# STHV800_breakout_board.net
KiCad netlist of a schematic drawn in EAGLE
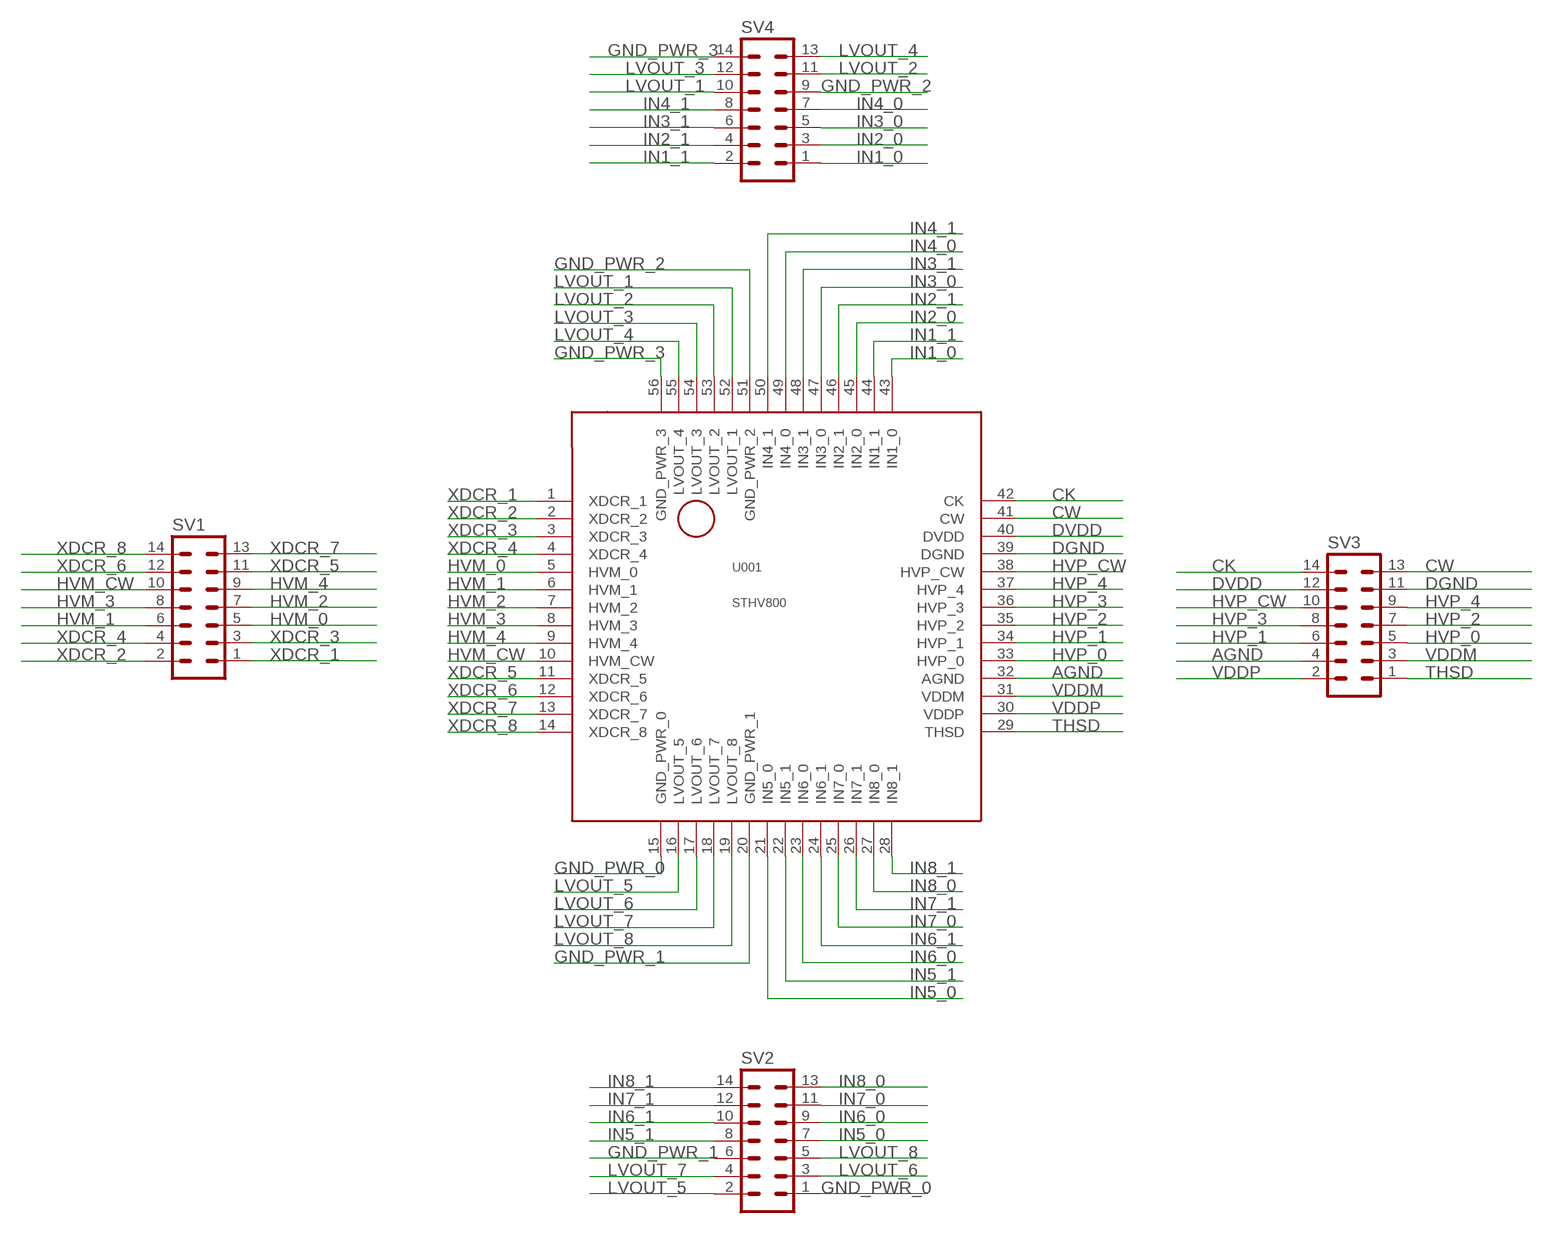
[diagram p0: schematic, sheet 1]

(export (version "E")
  (design (tool "Eeschema 10.0.6"))
  (components
    (comp (ref "SV1")
      (value "MA07-2")
      (footprint "eagle-import:MA07-2")
      (libsource (lib "eagle-import") (part "MA07-2"))
    )
    (comp (ref "SV2")
      (value "MA07-2")
      (footprint "eagle-import:MA07-2")
      (libsource (lib "eagle-import") (part "MA07-2"))
    )
    (comp (ref "SV3")
      (value "MA07-2")
      (footprint "eagle-import:MA07-2")
      (libsource (lib "eagle-import") (part "MA07-2"))
    )
    (comp (ref "SV4")
      (value "MA07-2")
      (footprint "eagle-import:MA07-2")
      (libsource (lib "eagle-import") (part "MA07-2"))
    )
    (comp (ref "U001")
      (value "STHV800")
      (footprint "eagle-import:STHV800")
      (libsource (lib "eagle-import") (part "STHV800"))
    )
  )
  (nets
    (net (code "1") (name "/AGND") (class "Default")
      (node (ref "SV3") (pin "4") (pinfunction "4_4") (pintype "passive"))
      (node (ref "U001") (pin "32") (pinfunction "AGND_32") (pintype "bidirectional"))
    )
    (net (code "2") (name "/CK") (class "Default")
      (node (ref "SV3") (pin "14") (pinfunction "14_14") (pintype "passive"))
      (node (ref "U001") (pin "42") (pinfunction "CK_42") (pintype "bidirectional"))
    )
    (net (code "3") (name "/CW") (class "Default")
      (node (ref "SV3") (pin "13") (pinfunction "13_13") (pintype "passive"))
      (node (ref "U001") (pin "41") (pinfunction "CW_41") (pintype "bidirectional"))
    )
    (net (code "4") (name "/DGND") (class "Default")
      (node (ref "SV3") (pin "11") (pinfunction "11_11") (pintype "passive"))
      (node (ref "U001") (pin "39") (pinfunction "DGND_39") (pintype "bidirectional"))
    )
    (net (code "5") (name "/DVDD") (class "Default")
      (node (ref "SV3") (pin "12") (pinfunction "12_12") (pintype "passive"))
      (node (ref "U001") (pin "40") (pinfunction "DVDD_40") (pintype "bidirectional"))
    )
    (net (code "6") (name "/GND_PWR_0") (class "Default")
      (node (ref "SV2") (pin "1") (pinfunction "1_1") (pintype "passive"))
      (node (ref "U001") (pin "15") (pinfunction "GND_PWR_0_15") (pintype "bidirectional"))
    )
    (net (code "7") (name "/GND_PWR_1") (class "Default")
      (node (ref "SV2") (pin "6") (pinfunction "6_6") (pintype "passive"))
      (node (ref "U001") (pin "20") (pinfunction "GND_PWR_1_20") (pintype "bidirectional"))
    )
    (net (code "8") (name "/GND_PWR_2") (class "Default")
      (node (ref "SV4") (pin "9") (pinfunction "9_9") (pintype "passive"))
      (node (ref "U001") (pin "51") (pinfunction "GND_PWR_2_51") (pintype "bidirectional"))
    )
    (net (code "9") (name "/GND_PWR_3") (class "Default")
      (node (ref "SV4") (pin "14") (pinfunction "14_14") (pintype "passive"))
      (node (ref "U001") (pin "56") (pinfunction "GND_PWR_3_56") (pintype "bidirectional"))
    )
    (net (code "10") (name "/HVM_0") (class "Default")
      (node (ref "SV1") (pin "5") (pinfunction "5_5") (pintype "passive"))
      (node (ref "U001") (pin "5") (pinfunction "HVM_0_5") (pintype "bidirectional"))
    )
    (net (code "11") (name "/HVM_1") (class "Default")
      (node (ref "SV1") (pin "6") (pinfunction "6_6") (pintype "passive"))
      (node (ref "U001") (pin "6") (pinfunction "HVM_1_6") (pintype "bidirectional"))
    )
    (net (code "12") (name "/HVM_2") (class "Default")
      (node (ref "SV1") (pin "7") (pinfunction "7_7") (pintype "passive"))
      (node (ref "U001") (pin "7") (pinfunction "HVM_2_7") (pintype "bidirectional"))
    )
    (net (code "13") (name "/HVM_3") (class "Default")
      (node (ref "SV1") (pin "8") (pinfunction "8_8") (pintype "passive"))
      (node (ref "U001") (pin "8") (pinfunction "HVM_3_8") (pintype "bidirectional"))
    )
    (net (code "14") (name "/HVM_4") (class "Default")
      (node (ref "SV1") (pin "9") (pinfunction "9_9") (pintype "passive"))
      (node (ref "U001") (pin "9") (pinfunction "HVM_4_9") (pintype "bidirectional"))
    )
    (net (code "15") (name "/HVM_CW") (class "Default")
      (node (ref "SV1") (pin "10") (pinfunction "10_10") (pintype "passive"))
      (node (ref "U001") (pin "10") (pinfunction "HVM_CW_10") (pintype "bidirectional"))
    )
    (net (code "16") (name "/HVP_0") (class "Default")
      (node (ref "SV3") (pin "5") (pinfunction "5_5") (pintype "passive"))
      (node (ref "U001") (pin "33") (pinfunction "HVP_0_33") (pintype "bidirectional"))
    )
    (net (code "17") (name "/HVP_1") (class "Default")
      (node (ref "SV3") (pin "6") (pinfunction "6_6") (pintype "passive"))
      (node (ref "U001") (pin "34") (pinfunction "HVP_1_34") (pintype "bidirectional"))
    )
    (net (code "18") (name "/HVP_2") (class "Default")
      (node (ref "SV3") (pin "7") (pinfunction "7_7") (pintype "passive"))
      (node (ref "U001") (pin "35") (pinfunction "HVP_2_35") (pintype "bidirectional"))
    )
    (net (code "19") (name "/HVP_3") (class "Default")
      (node (ref "SV3") (pin "8") (pinfunction "8_8") (pintype "passive"))
      (node (ref "U001") (pin "36") (pinfunction "HVP_3_36") (pintype "bidirectional"))
    )
    (net (code "20") (name "/HVP_4") (class "Default")
      (node (ref "SV3") (pin "9") (pinfunction "9_9") (pintype "passive"))
      (node (ref "U001") (pin "37") (pinfunction "HVP_4_37") (pintype "bidirectional"))
    )
    (net (code "21") (name "/HVP_CW") (class "Default")
      (node (ref "SV3") (pin "10") (pinfunction "10_10") (pintype "passive"))
      (node (ref "U001") (pin "38") (pinfunction "HVP_CW_38") (pintype "bidirectional"))
    )
    (net (code "22") (name "/IN1_0") (class "Default")
      (node (ref "SV4") (pin "1") (pinfunction "1_1") (pintype "passive"))
      (node (ref "U001") (pin "43") (pinfunction "IN1_0_43") (pintype "bidirectional"))
    )
    (net (code "23") (name "/IN1_1") (class "Default")
      (node (ref "SV4") (pin "2") (pinfunction "2_2") (pintype "passive"))
      (node (ref "U001") (pin "44") (pinfunction "IN1_1_44") (pintype "bidirectional"))
    )
    (net (code "24") (name "/IN2_0") (class "Default")
      (node (ref "SV4") (pin "3") (pinfunction "3_3") (pintype "passive"))
      (node (ref "U001") (pin "45") (pinfunction "IN2_0_45") (pintype "bidirectional"))
    )
    (net (code "25") (name "/IN2_1") (class "Default")
      (node (ref "SV4") (pin "4") (pinfunction "4_4") (pintype "passive"))
      (node (ref "U001") (pin "46") (pinfunction "IN2_1_46") (pintype "bidirectional"))
    )
    (net (code "26") (name "/IN3_0") (class "Default")
      (node (ref "SV4") (pin "5") (pinfunction "5_5") (pintype "passive"))
      (node (ref "U001") (pin "47") (pinfunction "IN3_0_47") (pintype "bidirectional"))
    )
    (net (code "27") (name "/IN3_1") (class "Default")
      (node (ref "SV4") (pin "6") (pinfunction "6_6") (pintype "passive"))
      (node (ref "U001") (pin "48") (pinfunction "IN3_1_48") (pintype "bidirectional"))
    )
    (net (code "28") (name "/IN4_0") (class "Default")
      (node (ref "SV4") (pin "7") (pinfunction "7_7") (pintype "passive"))
      (node (ref "U001") (pin "49") (pinfunction "IN4_0_49") (pintype "bidirectional"))
    )
    (net (code "29") (name "/IN4_1") (class "Default")
      (node (ref "SV4") (pin "8") (pinfunction "8_8") (pintype "passive"))
      (node (ref "U001") (pin "50") (pinfunction "IN4_1_50") (pintype "bidirectional"))
    )
    (net (code "30") (name "/IN5_0") (class "Default")
      (node (ref "SV2") (pin "7") (pinfunction "7_7") (pintype "passive"))
      (node (ref "U001") (pin "21") (pinfunction "IN5_0_21") (pintype "bidirectional"))
    )
    (net (code "31") (name "/IN5_1") (class "Default")
      (node (ref "SV2") (pin "8") (pinfunction "8_8") (pintype "passive"))
      (node (ref "U001") (pin "22") (pinfunction "IN5_1_22") (pintype "bidirectional"))
    )
    (net (code "32") (name "/IN6_0") (class "Default")
      (node (ref "SV2") (pin "9") (pinfunction "9_9") (pintype "passive"))
      (node (ref "U001") (pin "23") (pinfunction "IN6_0_23") (pintype "bidirectional"))
    )
    (net (code "33") (name "/IN6_1") (class "Default")
      (node (ref "SV2") (pin "10") (pinfunction "10_10") (pintype "passive"))
      (node (ref "U001") (pin "24") (pinfunction "IN6_1_24") (pintype "bidirectional"))
    )
    (net (code "34") (name "/IN7_0") (class "Default")
      (node (ref "SV2") (pin "11") (pinfunction "11_11") (pintype "passive"))
      (node (ref "U001") (pin "25") (pinfunction "IN7_0_25") (pintype "bidirectional"))
    )
    (net (code "35") (name "/IN7_1") (class "Default")
      (node (ref "SV2") (pin "12") (pinfunction "12_12") (pintype "passive"))
      (node (ref "U001") (pin "26") (pinfunction "IN7_1_26") (pintype "bidirectional"))
    )
    (net (code "36") (name "/IN8_0") (class "Default")
      (node (ref "SV2") (pin "13") (pinfunction "13_13") (pintype "passive"))
      (node (ref "U001") (pin "27") (pinfunction "IN8_0_27") (pintype "bidirectional"))
    )
    (net (code "37") (name "/IN8_1") (class "Default")
      (node (ref "SV2") (pin "14") (pinfunction "14_14") (pintype "passive"))
      (node (ref "U001") (pin "28") (pinfunction "IN8_1_28") (pintype "bidirectional"))
    )
    (net (code "38") (name "/LVOUT_1") (class "Default")
      (node (ref "SV4") (pin "10") (pinfunction "10_10") (pintype "passive"))
      (node (ref "U001") (pin "52") (pinfunction "LVOUT_1_52") (pintype "bidirectional"))
    )
    (net (code "39") (name "/LVOUT_2") (class "Default")
      (node (ref "SV4") (pin "11") (pinfunction "11_11") (pintype "passive"))
      (node (ref "U001") (pin "53") (pinfunction "LVOUT_2_53") (pintype "bidirectional"))
    )
    (net (code "40") (name "/LVOUT_3") (class "Default")
      (node (ref "SV4") (pin "12") (pinfunction "12_12") (pintype "passive"))
      (node (ref "U001") (pin "54") (pinfunction "LVOUT_3_54") (pintype "bidirectional"))
    )
    (net (code "41") (name "/LVOUT_4") (class "Default")
      (node (ref "SV4") (pin "13") (pinfunction "13_13") (pintype "passive"))
      (node (ref "U001") (pin "55") (pinfunction "LVOUT_4_55") (pintype "bidirectional"))
    )
    (net (code "42") (name "/LVOUT_5") (class "Default")
      (node (ref "SV2") (pin "2") (pinfunction "2_2") (pintype "passive"))
      (node (ref "U001") (pin "16") (pinfunction "LVOUT_5_16") (pintype "bidirectional"))
    )
    (net (code "43") (name "/LVOUT_6") (class "Default")
      (node (ref "SV2") (pin "3") (pinfunction "3_3") (pintype "passive"))
      (node (ref "U001") (pin "17") (pinfunction "LVOUT_6_17") (pintype "bidirectional"))
    )
    (net (code "44") (name "/LVOUT_7") (class "Default")
      (node (ref "SV2") (pin "4") (pinfunction "4_4") (pintype "passive"))
      (node (ref "U001") (pin "18") (pinfunction "LVOUT_7_18") (pintype "bidirectional"))
    )
    (net (code "45") (name "/LVOUT_8") (class "Default")
      (node (ref "SV2") (pin "5") (pinfunction "5_5") (pintype "passive"))
      (node (ref "U001") (pin "19") (pinfunction "LVOUT_8_19") (pintype "bidirectional"))
    )
    (net (code "46") (name "/THSD") (class "Default")
      (node (ref "SV3") (pin "1") (pinfunction "1_1") (pintype "passive"))
      (node (ref "U001") (pin "29") (pinfunction "THSD_29") (pintype "bidirectional"))
    )
    (net (code "47") (name "/VDDM") (class "Default")
      (node (ref "SV3") (pin "3") (pinfunction "3_3") (pintype "passive"))
      (node (ref "U001") (pin "31") (pinfunction "VDDM_31") (pintype "bidirectional"))
    )
    (net (code "48") (name "/VDDP") (class "Default")
      (node (ref "SV3") (pin "2") (pinfunction "2_2") (pintype "passive"))
      (node (ref "U001") (pin "30") (pinfunction "VDDP_30") (pintype "bidirectional"))
    )
    (net (code "49") (name "/XDCR_1") (class "Default")
      (node (ref "SV1") (pin "1") (pinfunction "1_1") (pintype "passive"))
      (node (ref "U001") (pin "1") (pinfunction "XDCR_1_1") (pintype "bidirectional"))
    )
    (net (code "50") (name "/XDCR_2") (class "Default")
      (node (ref "SV1") (pin "2") (pinfunction "2_2") (pintype "passive"))
      (node (ref "U001") (pin "2") (pinfunction "XDCR_2_2") (pintype "bidirectional"))
    )
    (net (code "51") (name "/XDCR_3") (class "Default")
      (node (ref "SV1") (pin "3") (pinfunction "3_3") (pintype "passive"))
      (node (ref "U001") (pin "3") (pinfunction "XDCR_3_3") (pintype "bidirectional"))
    )
    (net (code "52") (name "/XDCR_4") (class "Default")
      (node (ref "SV1") (pin "4") (pinfunction "4_4") (pintype "passive"))
      (node (ref "U001") (pin "4") (pinfunction "XDCR_4_4") (pintype "bidirectional"))
    )
    (net (code "53") (name "/XDCR_5") (class "Default")
      (node (ref "SV1") (pin "11") (pinfunction "11_11") (pintype "passive"))
      (node (ref "U001") (pin "11") (pinfunction "XDCR_5_11") (pintype "bidirectional"))
    )
    (net (code "54") (name "/XDCR_6") (class "Default")
      (node (ref "SV1") (pin "12") (pinfunction "12_12") (pintype "passive"))
      (node (ref "U001") (pin "12") (pinfunction "XDCR_6_12") (pintype "bidirectional"))
    )
    (net (code "55") (name "/XDCR_7") (class "Default")
      (node (ref "SV1") (pin "13") (pinfunction "13_13") (pintype "passive"))
      (node (ref "U001") (pin "13") (pinfunction "XDCR_7_13") (pintype "bidirectional"))
    )
    (net (code "56") (name "/XDCR_8") (class "Default")
      (node (ref "SV1") (pin "14") (pinfunction "14_14") (pintype "passive"))
      (node (ref "U001") (pin "14") (pinfunction "XDCR_8_14") (pintype "bidirectional"))
    )
  )
)
